# ProPrj___2025-07-03.net
KiCad netlist of a schematic drawn in EasyEDA Pro
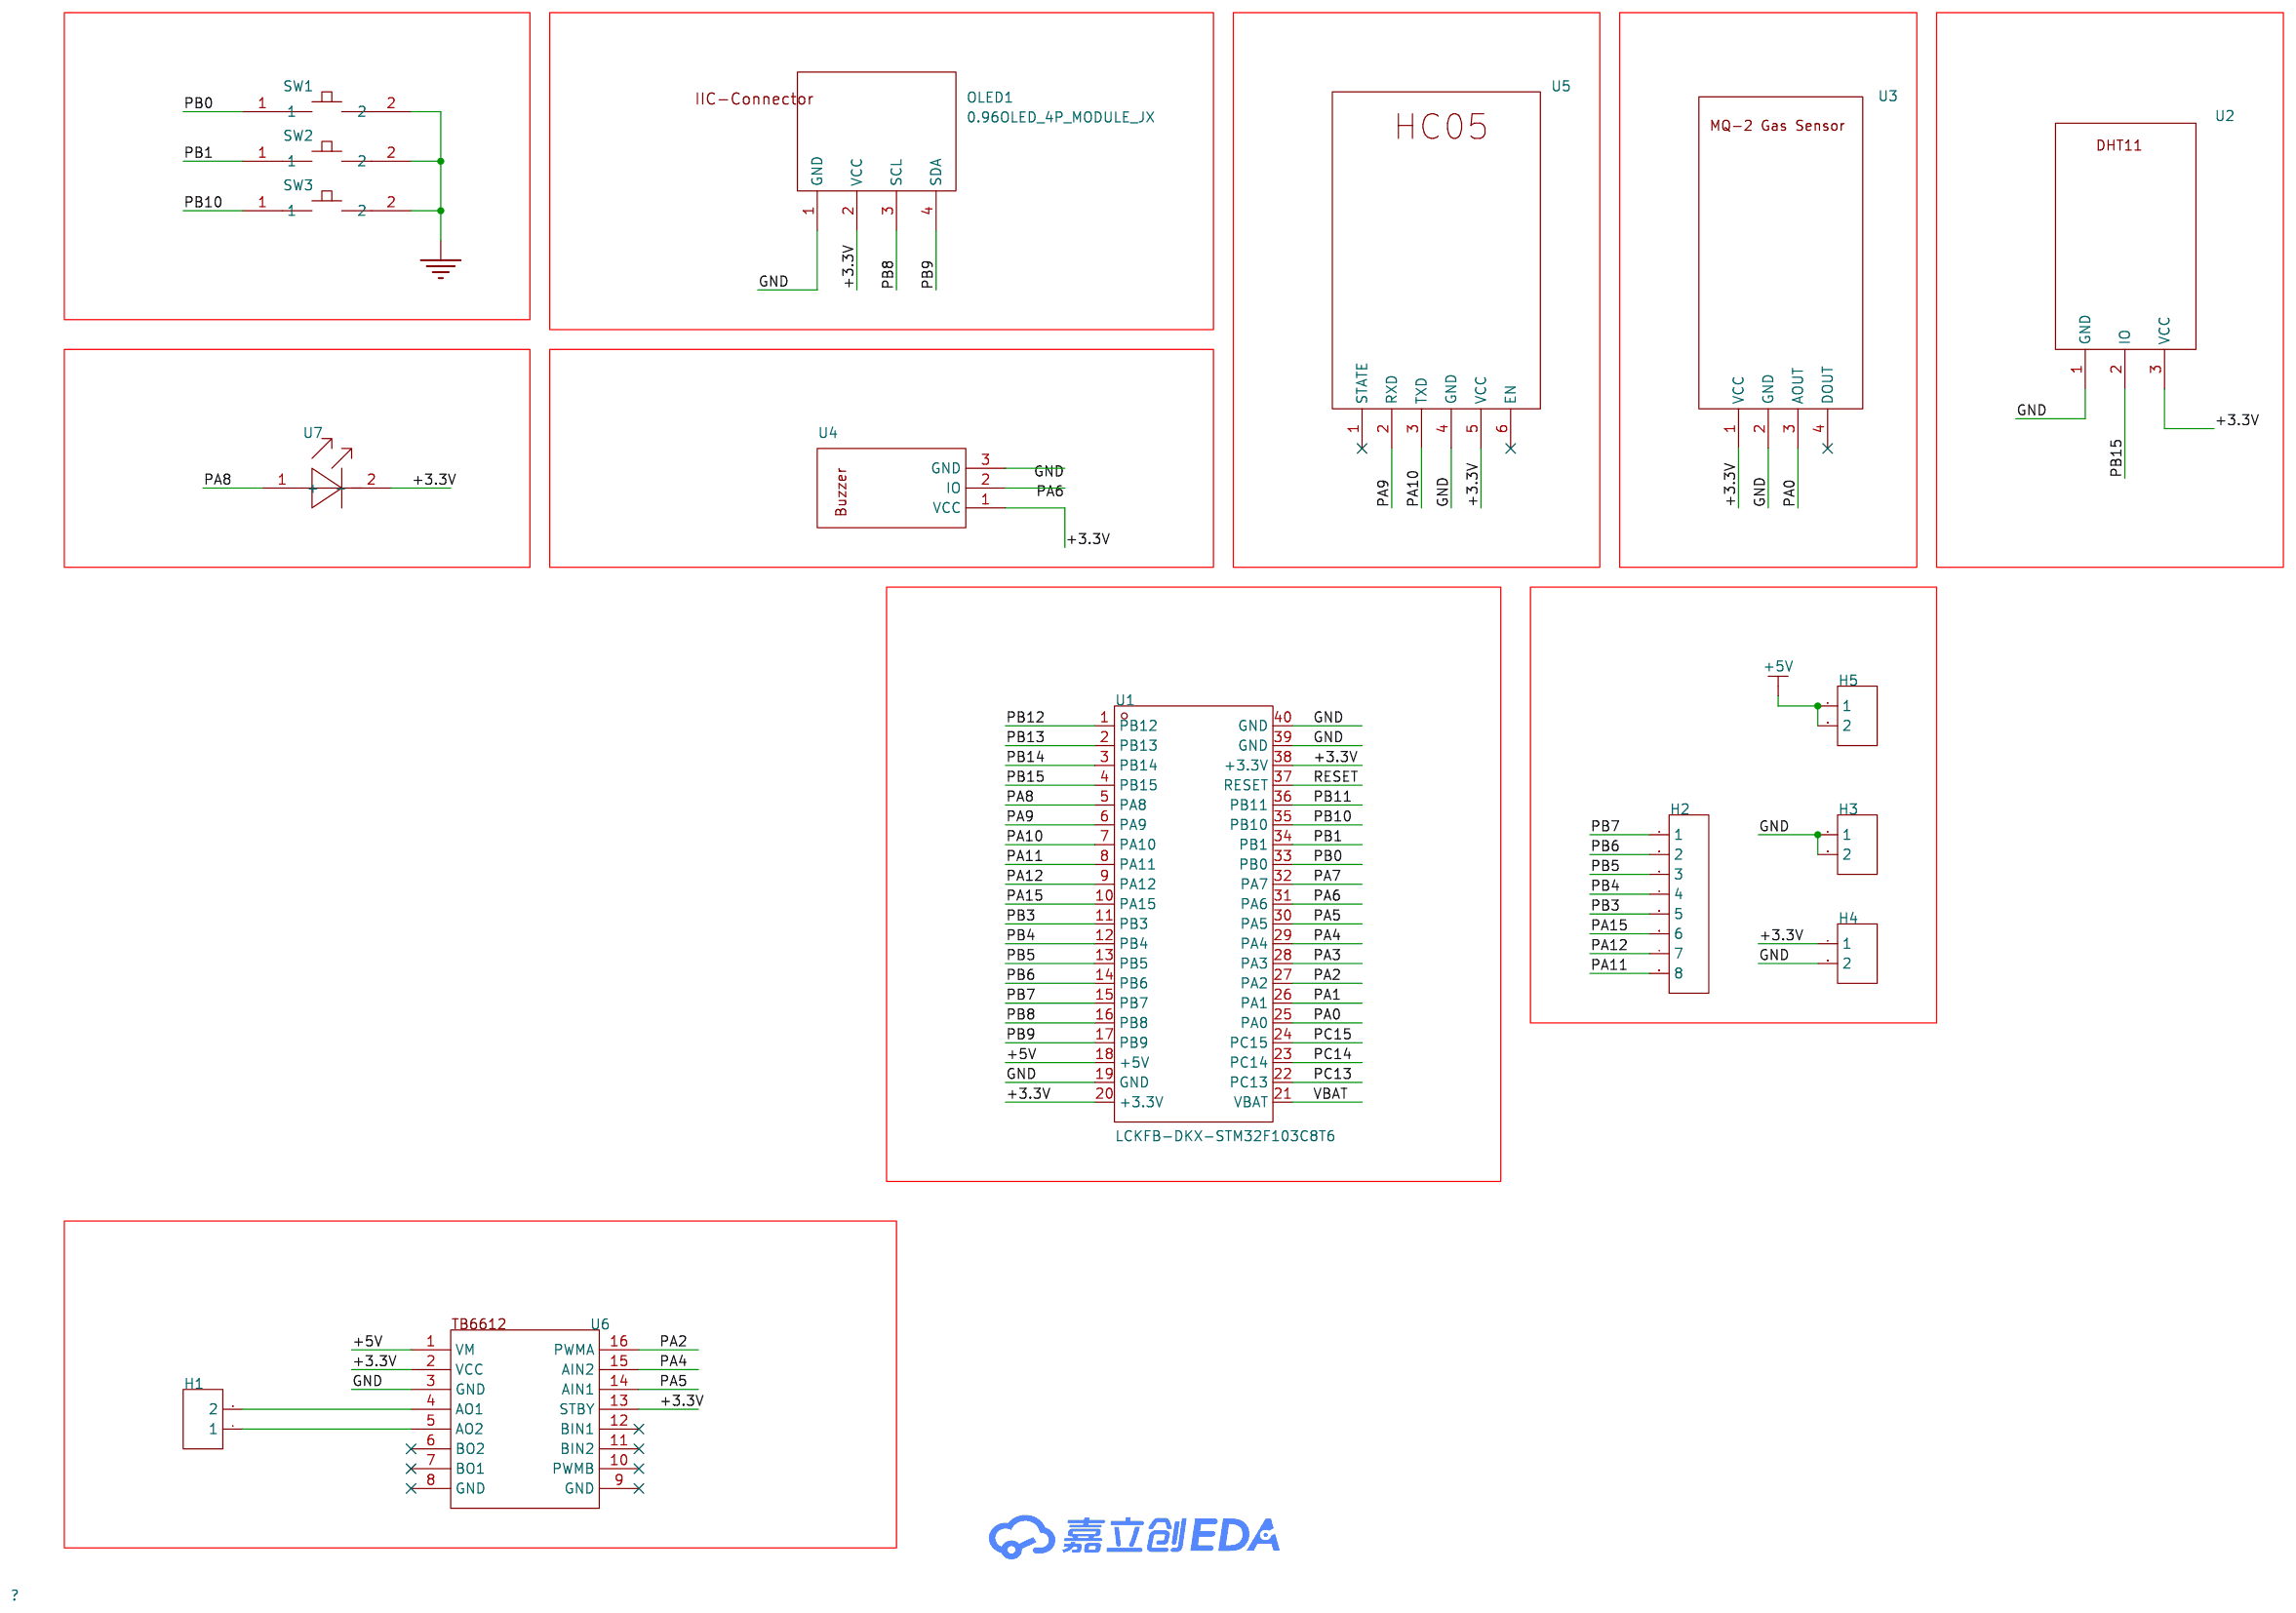
[diagram p0: schematic sheet]

(export (version "E")
  (design (tool "Eeschema 10.0.6"))
  (components
    (comp (ref "H1")
      (value "~")
      (footprint "easyedapro:HDR-TH_2P-P2.54-V-F")
      (libsource (lib "easyedapro") (part "Header-Female-2.54_1x2"))
    )
    (comp (ref "H2")
      (value "~")
      (footprint "easyedapro:HDR-TH_8P-P2.54-V-F-1")
      (libsource (lib "easyedapro") (part "Header-Female-2.54_1x8"))
    )
    (comp (ref "H3")
      (value "~")
      (footprint "easyedapro:HDR-TH_2P-P2.54-V-F")
      (libsource (lib "easyedapro") (part "Header-Female-2.54_1x2"))
    )
    (comp (ref "H4")
      (value "~")
      (footprint "easyedapro:HDR-TH_2P-P2.54-V-F")
      (libsource (lib "easyedapro") (part "Header-Female-2.54_1x2"))
    )
    (comp (ref "H5")
      (value "~")
      (footprint "easyedapro:HDR-TH_2P-P2.54-V-F")
      (libsource (lib "easyedapro") (part "Header-Female-2.54_1x2"))
    )
    (comp (ref "OLED1")
      (value "0.96OLED_4P_MODULE_JX")
      (footprint "easyedapro:0.96OLED_4P")
      (libsource (lib "easyedapro") (part "0.96OLED_4P_MODULE_JX"))
    )
    (comp (ref "SW1") (value "~") (footprint "easyedapro:按键") (libsource (lib "easyedapro") (part "按键")))
    (comp (ref "SW2") (value "~") (footprint "easyedapro:按键") (libsource (lib "easyedapro") (part "按键")))
    (comp (ref "SW3") (value "~") (footprint "easyedapro:按键") (libsource (lib "easyedapro") (part "按键")))
    (comp (ref "U1")
      (value "LCKFB-DKX-STM32F103C8T6")
      (footprint "easyedapro:CONN-TH_L53.3-W22.9_STM32F103C8T6-CARD")
      (fields (field (name "Manufacturer") "立创开发板"))
      (libsource (lib "easyedapro") (part "LCKFB-DKX-STM32F103C8T6"))
    )
    (comp (ref "U2")
      (value "~")
      (footprint "easyedapro:DHT11.")
      (libsource (lib "easyedapro") (part "DHT11"))
    )
    (comp (ref "U3")
      (value "~")
      (footprint "easyedapro:MQ-2 Gas Sensor")
      (libsource (lib "easyedapro") (part "MQ-2 Gas Sensor"))
    )
    (comp (ref "U4")
      (value "~")
      (footprint "easyedapro:Buzzer")
      (libsource (lib "easyedapro") (part "Buzzer"))
    )
    (comp (ref "U5") (value "~") (footprint "easyedapro:HC05") (libsource (lib "easyedapro") (part "HC05")))
    (comp (ref "U6")
      (value "~")
      (footprint "easyedapro:TB6612")
      (libsource (lib "easyedapro") (part "TB6612"))
    )
    (comp (ref "U7") (value "~") (footprint "easyedapro:LED") (libsource (lib "easyedapro") (part "LED")))
  )
  (nets
    (net (code "1") (name "+5V") (class "Default")
      (node (ref "H5") (pin "1") (pinfunction "1_1") (pintype "input"))
      (node (ref "H5") (pin "2") (pinfunction "2_2") (pintype "input"))
      (node (ref "U1") (pin "18") (pinfunction "+5V_18") (pintype "unspecified"))
      (node (ref "U6") (pin "1") (pinfunction "VM_1") (pintype "input"))
    )
    (net (code "2") (name "/+3.3V") (class "Default")
      (node (ref "H4") (pin "1") (pinfunction "1_1") (pintype "input"))
      (node (ref "OLED1") (pin "2") (pinfunction "VCC_2") (pintype "unspecified"))
      (node (ref "U1") (pin "20") (pinfunction "+3.3V_20") (pintype "unspecified"))
      (node (ref "U1") (pin "38") (pinfunction "+3.3V_38") (pintype "unspecified"))
      (node (ref "U2") (pin "3") (pinfunction "VCC_3") (pintype "input"))
      (node (ref "U3") (pin "1") (pinfunction "VCC_1") (pintype "input"))
      (node (ref "U4") (pin "1") (pinfunction "VCC_1") (pintype "input"))
      (node (ref "U5") (pin "5") (pinfunction "VCC_5") (pintype "input"))
      (node (ref "U6") (pin "13") (pinfunction "STBY_13") (pintype "input"))
      (node (ref "U6") (pin "2") (pinfunction "VCC_2") (pintype "input"))
      (node (ref "U7") (pin "2") (pinfunction "-_2") (pintype "input"))
    )
    (net (code "3") (name "/PA0") (class "Default")
      (node (ref "U1") (pin "25") (pinfunction "PA0_25") (pintype "unspecified"))
      (node (ref "U3") (pin "3") (pinfunction "AOUT_3") (pintype "input"))
    )
    (net (code "4") (name "/PA1") (class "Default")
      (node (ref "U1") (pin "26") (pinfunction "PA1_26") (pintype "unspecified"))
    )
    (net (code "5") (name "/PA2") (class "Default")
      (node (ref "U1") (pin "27") (pinfunction "PA2_27") (pintype "unspecified"))
      (node (ref "U6") (pin "16") (pinfunction "PWMA_16") (pintype "input"))
    )
    (net (code "6") (name "/PA3") (class "Default")
      (node (ref "U1") (pin "28") (pinfunction "PA3_28") (pintype "unspecified"))
    )
    (net (code "7") (name "/PA4") (class "Default")
      (node (ref "U1") (pin "29") (pinfunction "PA4_29") (pintype "unspecified"))
      (node (ref "U6") (pin "15") (pinfunction "AIN2_15") (pintype "input"))
    )
    (net (code "8") (name "/PA5") (class "Default")
      (node (ref "U1") (pin "30") (pinfunction "PA5_30") (pintype "unspecified"))
      (node (ref "U6") (pin "14") (pinfunction "AIN1_14") (pintype "input"))
    )
    (net (code "9") (name "/PA6") (class "Default")
      (node (ref "U1") (pin "31") (pinfunction "PA6_31") (pintype "unspecified"))
      (node (ref "U4") (pin "2") (pinfunction "IO_2") (pintype "input"))
    )
    (net (code "10") (name "/PA7") (class "Default")
      (node (ref "U1") (pin "32") (pinfunction "PA7_32") (pintype "unspecified"))
    )
    (net (code "11") (name "/PA8") (class "Default")
      (node (ref "U1") (pin "5") (pinfunction "PA8_5") (pintype "unspecified"))
      (node (ref "U7") (pin "1") (pinfunction "+_1") (pintype "input"))
    )
    (net (code "12") (name "/PA9") (class "Default")
      (node (ref "U1") (pin "6") (pinfunction "PA9_6") (pintype "unspecified"))
      (node (ref "U5") (pin "2") (pinfunction "RXD_2") (pintype "input"))
    )
    (net (code "13") (name "/PA10") (class "Default")
      (node (ref "U1") (pin "7") (pinfunction "PA10_7") (pintype "unspecified"))
      (node (ref "U5") (pin "3") (pinfunction "TXD_3") (pintype "input"))
    )
    (net (code "14") (name "/PA11") (class "Default")
      (node (ref "H2") (pin "8") (pinfunction "8_8") (pintype "input"))
      (node (ref "U1") (pin "8") (pinfunction "PA11_8") (pintype "unspecified"))
    )
    (net (code "15") (name "/PA12") (class "Default")
      (node (ref "H2") (pin "7") (pinfunction "7_7") (pintype "input"))
      (node (ref "U1") (pin "9") (pinfunction "PA12_9") (pintype "unspecified"))
    )
    (net (code "16") (name "/PA15") (class "Default")
      (node (ref "H2") (pin "6") (pinfunction "6_6") (pintype "input"))
      (node (ref "U1") (pin "10") (pinfunction "PA15_10") (pintype "unspecified"))
    )
    (net (code "17") (name "/PB0") (class "Default")
      (node (ref "SW1") (pin "1") (pinfunction "1_1") (pintype "input"))
      (node (ref "U1") (pin "33") (pinfunction "PB0_33") (pintype "unspecified"))
    )
    (net (code "18") (name "/PB1") (class "Default")
      (node (ref "SW2") (pin "1") (pinfunction "1_1") (pintype "input"))
      (node (ref "U1") (pin "34") (pinfunction "PB1_34") (pintype "unspecified"))
    )
    (net (code "19") (name "/PB3") (class "Default")
      (node (ref "H2") (pin "5") (pinfunction "5_5") (pintype "input"))
      (node (ref "U1") (pin "11") (pinfunction "PB3_11") (pintype "unspecified"))
    )
    (net (code "20") (name "/PB4") (class "Default")
      (node (ref "H2") (pin "4") (pinfunction "4_4") (pintype "input"))
      (node (ref "U1") (pin "12") (pinfunction "PB4_12") (pintype "unspecified"))
    )
    (net (code "21") (name "/PB5") (class "Default")
      (node (ref "H2") (pin "3") (pinfunction "3_3") (pintype "input"))
      (node (ref "U1") (pin "13") (pinfunction "PB5_13") (pintype "unspecified"))
    )
    (net (code "22") (name "/PB6") (class "Default")
      (node (ref "H2") (pin "2") (pinfunction "2_2") (pintype "input"))
      (node (ref "U1") (pin "14") (pinfunction "PB6_14") (pintype "unspecified"))
    )
    (net (code "23") (name "/PB7") (class "Default")
      (node (ref "H2") (pin "1") (pinfunction "1_1") (pintype "input"))
      (node (ref "U1") (pin "15") (pinfunction "PB7_15") (pintype "unspecified"))
    )
    (net (code "24") (name "/PB8") (class "Default")
      (node (ref "OLED1") (pin "3") (pinfunction "SCL_3") (pintype "unspecified"))
      (node (ref "U1") (pin "16") (pinfunction "PB8_16") (pintype "unspecified"))
    )
    (net (code "25") (name "/PB9") (class "Default")
      (node (ref "OLED1") (pin "4") (pinfunction "SDA_4") (pintype "unspecified"))
      (node (ref "U1") (pin "17") (pinfunction "PB9_17") (pintype "unspecified"))
    )
    (net (code "26") (name "/PB10") (class "Default")
      (node (ref "SW3") (pin "1") (pinfunction "1_1") (pintype "input"))
      (node (ref "U1") (pin "35") (pinfunction "PB10_35") (pintype "unspecified"))
    )
    (net (code "27") (name "/PB11") (class "Default")
      (node (ref "U1") (pin "36") (pinfunction "PB11_36") (pintype "unspecified"))
    )
    (net (code "28") (name "/PB12") (class "Default")
      (node (ref "U1") (pin "1") (pinfunction "PB12_1") (pintype "unspecified"))
    )
    (net (code "29") (name "/PB13") (class "Default")
      (node (ref "U1") (pin "2") (pinfunction "PB13_2") (pintype "unspecified"))
    )
    (net (code "30") (name "/PB14") (class "Default")
      (node (ref "U1") (pin "3") (pinfunction "PB14_3") (pintype "unspecified"))
    )
    (net (code "31") (name "/PB15") (class "Default")
      (node (ref "U1") (pin "4") (pinfunction "PB15_4") (pintype "unspecified"))
      (node (ref "U2") (pin "2") (pinfunction "IO_2") (pintype "input"))
    )
    (net (code "32") (name "/PC13") (class "Default")
      (node (ref "U1") (pin "22") (pinfunction "PC13_22") (pintype "unspecified"))
    )
    (net (code "33") (name "/PC14") (class "Default")
      (node (ref "U1") (pin "23") (pinfunction "PC14_23") (pintype "unspecified"))
    )
    (net (code "34") (name "/PC15") (class "Default")
      (node (ref "U1") (pin "24") (pinfunction "PC15_24") (pintype "unspecified"))
    )
    (net (code "35") (name "/RESET") (class "Default")
      (node (ref "U1") (pin "37") (pinfunction "RESET_37") (pintype "unspecified"))
    )
    (net (code "36") (name "/VBAT") (class "Default")
      (node (ref "U1") (pin "21") (pinfunction "VBAT_21") (pintype "unspecified"))
    )
    (net (code "37") (name "GND") (class "Default")
      (node (ref "H3") (pin "1") (pinfunction "1_1") (pintype "input"))
      (node (ref "H3") (pin "2") (pinfunction "2_2") (pintype "input"))
      (node (ref "H4") (pin "2") (pinfunction "2_2") (pintype "input"))
      (node (ref "OLED1") (pin "1") (pinfunction "GND_1") (pintype "unspecified"))
      (node (ref "SW1") (pin "2") (pinfunction "2_2") (pintype "input"))
      (node (ref "SW2") (pin "2") (pinfunction "2_2") (pintype "input"))
      (node (ref "SW3") (pin "2") (pinfunction "2_2") (pintype "input"))
      (node (ref "U1") (pin "19") (pinfunction "GND_19") (pintype "unspecified"))
      (node (ref "U1") (pin "39") (pinfunction "GND_39") (pintype "unspecified"))
      (node (ref "U1") (pin "40") (pinfunction "GND_40") (pintype "unspecified"))
      (node (ref "U2") (pin "1") (pinfunction "GND_1") (pintype "input"))
      (node (ref "U3") (pin "2") (pinfunction "GND_2") (pintype "input"))
      (node (ref "U4") (pin "3") (pinfunction "GND_3") (pintype "input"))
      (node (ref "U5") (pin "4") (pinfunction "GND_4") (pintype "input"))
      (node (ref "U6") (pin "3") (pinfunction "GND_3") (pintype "input"))
    )
    (net (code "38") (name "Net-(U6-AO1)") (class "Default")
      (node (ref "H1") (pin "2") (pinfunction "2_2") (pintype "input"))
      (node (ref "U6") (pin "4") (pinfunction "AO1_4") (pintype "input"))
    )
    (net (code "39") (name "Net-(U6-AO2)") (class "Default")
      (node (ref "H1") (pin "1") (pinfunction "1_1") (pintype "input"))
      (node (ref "U6") (pin "5") (pinfunction "AO2_5") (pintype "input"))
    )
    (net (code "40") (name "unconnected-(U3-DOUT-Pad4)") (class "Default")
      (node (ref "U3") (pin "4") (pinfunction "DOUT_4") (pintype "input+no_connect"))
    )
    (net (code "41") (name "unconnected-(U5-EN-Pad6)") (class "Default")
      (node (ref "U5") (pin "6") (pinfunction "EN_6") (pintype "input+no_connect"))
    )
    (net (code "42") (name "unconnected-(U5-STATE-Pad1)") (class "Default")
      (node (ref "U5") (pin "1") (pinfunction "STATE_1") (pintype "input+no_connect"))
    )
    (net (code "43") (name "unconnected-(U6-BIN1-Pad12)") (class "Default")
      (node (ref "U6") (pin "12") (pinfunction "BIN1_12") (pintype "input+no_connect"))
    )
    (net (code "44") (name "unconnected-(U6-BIN2-Pad11)") (class "Default")
      (node (ref "U6") (pin "11") (pinfunction "BIN2_11") (pintype "input+no_connect"))
    )
    (net (code "45") (name "unconnected-(U6-BO1-Pad7)") (class "Default")
      (node (ref "U6") (pin "7") (pinfunction "BO1_7") (pintype "input+no_connect"))
    )
    (net (code "46") (name "unconnected-(U6-BO2-Pad6)") (class "Default")
      (node (ref "U6") (pin "6") (pinfunction "BO2_6") (pintype "input+no_connect"))
    )
    (net (code "47") (name "unconnected-(U6-GND-Pad8)") (class "Default")
      (node (ref "U6") (pin "8") (pinfunction "GND_8") (pintype "input+no_connect"))
    )
    (net (code "48") (name "unconnected-(U6-GND-Pad9)") (class "Default")
      (node (ref "U6") (pin "9") (pinfunction "GND_9") (pintype "input+no_connect"))
    )
    (net (code "49") (name "unconnected-(U6-PWMB-Pad10)") (class "Default")
      (node (ref "U6") (pin "10") (pinfunction "PWMB_10") (pintype "input+no_connect"))
    )
  )
)
